# core.net
KiCad netlist of a schematic drawn in Altium Designer
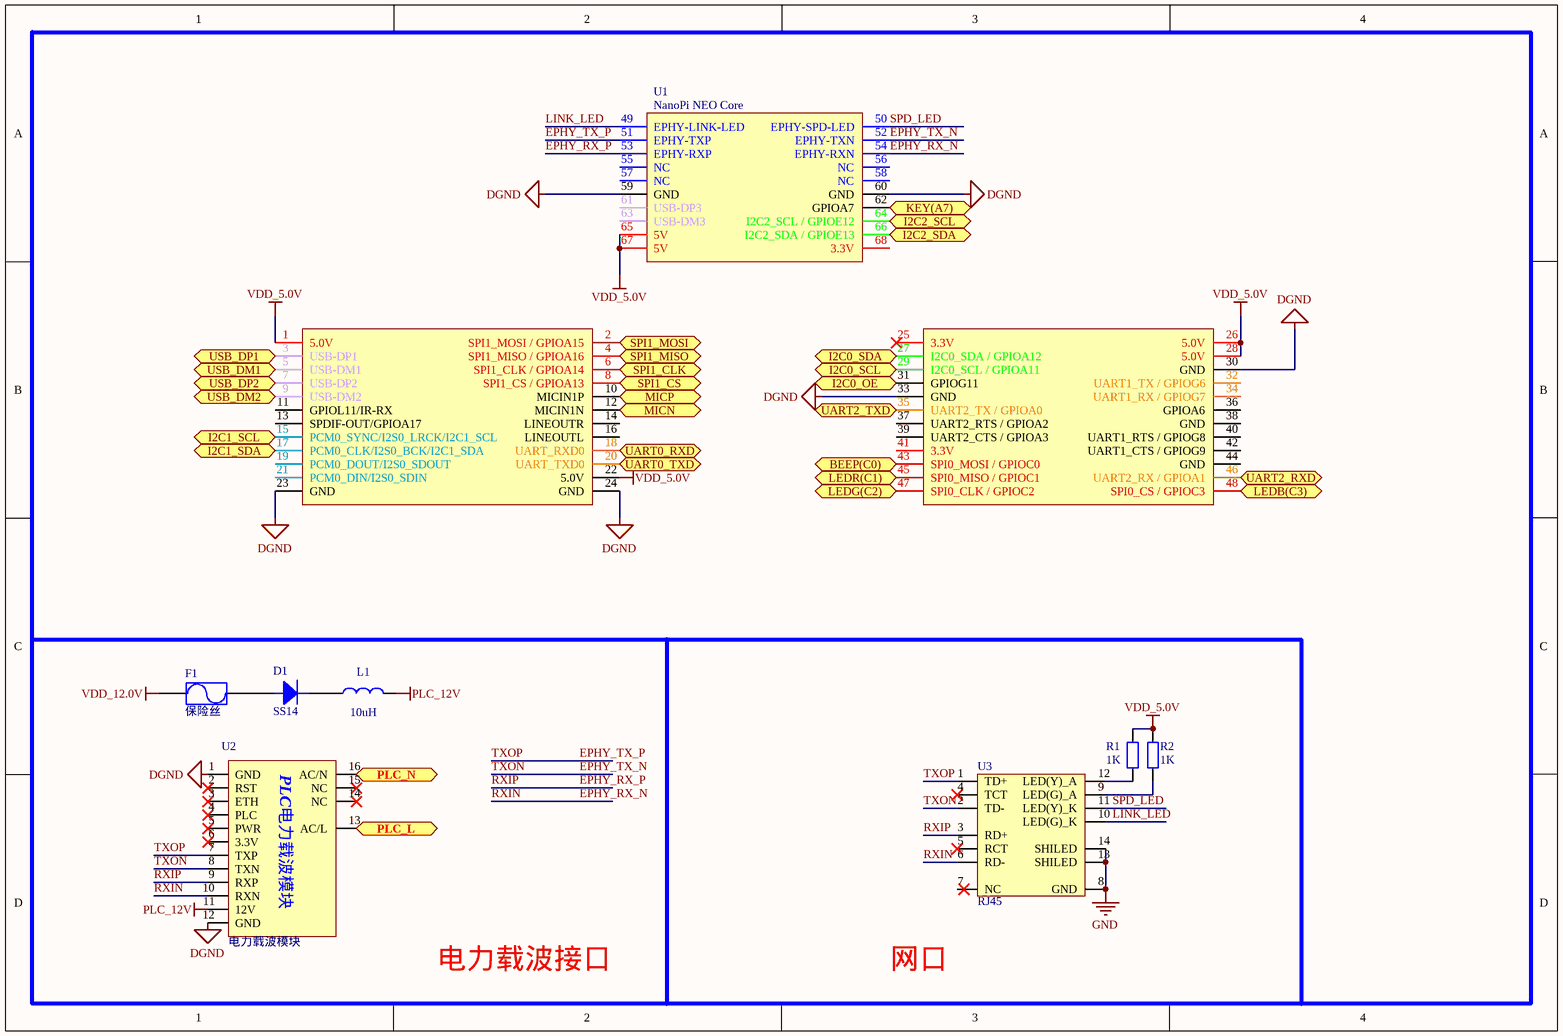
[diagram p0: core.SchDoc]

(export (version "E")
  (design (tool "Eeschema 10.0.6"))
  (components
    (comp (ref "D1")
      (value "SS14")
      (footprint "SMA/DO-214AC")
      (description "二极管")
      (libsource (lib "集大电协1.5") (part "Diode"))
    )
    (comp (ref "F1") (value "保险丝") (footprint "FUSE-1206") (libsource (lib "集大电协1.5") (part "Fuse")))
    (comp (ref "L1")
      (value "10uH")
      (footprint "1206L")
      (description "电感")
      (libsource (lib "集大电协1.5") (part "L"))
    )
    (comp (ref "R1")
      (value "1K")
      (footprint "0805R")
      (description "电阻")
      (libsource (lib "集大电协1.5") (part "Res"))
    )
    (comp (ref "R2")
      (value "1K")
      (footprint "0805R")
      (description "电阻")
      (libsource (lib "集大电协1.5") (part "Res"))
    )
    (comp (ref "U1")
      (value "NanoPi NEO Core")
      (footprint "NanoPi NEO Core")
      (libsource (lib "集大电协1.5") (part "NanoPi NEO Core"))
    )
    (comp (ref "U2")
      (value "电力载波模块")
      (footprint "电力载波模块6410")
      (libsource (lib "集大电协1.2") (part "电力载波模块6410"))
    )
    (comp (ref "U3") (value "RJ45") (footprint "RJ45") (libsource (lib "集大电协1.5") (part "RJ45")))
  )
  (nets
    (net (code "1") (name "/BEEP(C0)") (class "Default")
      (node (ref "U1") (pin "43") (pinfunction "SPI0_MOSI_/_GPIOC0_43") (pintype "passive"))
    )
    (net (code "2") (name "/EPHY_RX_N") (class "Default")
      (node (ref "U1") (pin "54") (pinfunction "EPHY-RXN_54") (pintype "passive"))
      (node (ref "U2") (pin "10") (pinfunction "RXN_10") (pintype "passive"))
      (node (ref "U3") (pin "6") (pinfunction "RD-_6") (pintype "passive"))
    )
    (net (code "3") (name "/EPHY_RX_P") (class "Default")
      (node (ref "U1") (pin "53") (pinfunction "EPHY-RXP_53") (pintype "passive"))
      (node (ref "U2") (pin "9") (pinfunction "RXP_9") (pintype "passive"))
      (node (ref "U3") (pin "3") (pinfunction "RD+_3") (pintype "passive"))
    )
    (net (code "4") (name "/EPHY_TX_N") (class "Default")
      (node (ref "U1") (pin "52") (pinfunction "EPHY-TXN_52") (pintype "passive"))
      (node (ref "U2") (pin "8") (pinfunction "TXN_8") (pintype "passive"))
      (node (ref "U3") (pin "2") (pinfunction "TD-_2") (pintype "passive"))
    )
    (net (code "5") (name "/EPHY_TX_P") (class "Default")
      (node (ref "U1") (pin "51") (pinfunction "EPHY-TXP_51") (pintype "passive"))
      (node (ref "U2") (pin "7") (pinfunction "TXP_7") (pintype "passive"))
      (node (ref "U3") (pin "1") (pinfunction "TD+_1") (pintype "passive"))
    )
    (net (code "6") (name "/I2C0_OE") (class "Default")
      (node (ref "U1") (pin "31") (pinfunction "GPIOG11_31") (pintype "passive"))
    )
    (net (code "7") (name "/I2C0_SCL") (class "Default")
      (node (ref "U1") (pin "29") (pinfunction "I2C0_SCL_/_GPIOA11_29") (pintype "passive"))
    )
    (net (code "8") (name "/I2C0_SDA") (class "Default")
      (node (ref "U1") (pin "27") (pinfunction "I2C0_SDA_/_GPIOA12_27") (pintype "passive"))
    )
    (net (code "9") (name "/I2C1_SCL") (class "Default")
      (node (ref "U1") (pin "15") (pinfunction "PCM0_SYNC/I2S0_LRCK/I2C1_SCL_15") (pintype "passive"))
    )
    (net (code "10") (name "/I2C1_SDA") (class "Default")
      (node (ref "U1") (pin "17") (pinfunction "PCM0_CLK/I2S0_BCK/I2C1_SDA_17") (pintype "passive"))
    )
    (net (code "11") (name "/I2C2_SCL") (class "Default")
      (node (ref "U1") (pin "64") (pinfunction "I2C2_SCL_/_GPIOE12_64") (pintype "passive"))
    )
    (net (code "12") (name "/I2C2_SDA") (class "Default")
      (node (ref "U1") (pin "66") (pinfunction "I2C2_SDA_/_GPIOE13_66") (pintype "passive"))
    )
    (net (code "13") (name "/KEY(A7)") (class "Default")
      (node (ref "U1") (pin "62") (pinfunction "GPIOA7_62") (pintype "passive"))
    )
    (net (code "14") (name "/LEDB(C3)") (class "Default")
      (node (ref "U1") (pin "48") (pinfunction "SPI0_CS_/_GPIOC3_48") (pintype "passive"))
    )
    (net (code "15") (name "/LEDG(C2)") (class "Default")
      (node (ref "U1") (pin "47") (pinfunction "SPI0_CLK_/_GPIOC2_47") (pintype "passive"))
    )
    (net (code "16") (name "/LEDR(C1)") (class "Default")
      (node (ref "U1") (pin "45") (pinfunction "SPI0_MISO_/_GPIOC1_45") (pintype "passive"))
    )
    (net (code "17") (name "/LINK_LED") (class "Default")
      (node (ref "U1") (pin "49") (pinfunction "EPHY-LINK-LED_49") (pintype "passive"))
      (node (ref "U3") (pin "10") (pinfunction "LED(G)_K_10") (pintype "passive"))
    )
    (net (code "18") (name "/MICN") (class "Default")
      (node (ref "U1") (pin "12") (pinfunction "MICIN1N_12") (pintype "passive"))
    )
    (net (code "19") (name "/MICP") (class "Default")
      (node (ref "U1") (pin "10") (pinfunction "MICIN1P_10") (pintype "passive"))
    )
    (net (code "20") (name "/PLC_L") (class "Default")
      (node (ref "U2") (pin "13") (pinfunction "AC/L_13") (pintype "passive"))
    )
    (net (code "21") (name "/PLC_N") (class "Default")
      (node (ref "U2") (pin "16") (pinfunction "AC/N_16") (pintype "passive"))
    )
    (net (code "22") (name "/SPD_LED") (class "Default")
      (node (ref "U1") (pin "50") (pinfunction "EPHY-SPD-LED_50") (pintype "passive"))
      (node (ref "U3") (pin "11") (pinfunction "LED(Y)_K_11") (pintype "passive"))
    )
    (net (code "23") (name "/SPI1_CLK") (class "Default")
      (node (ref "U1") (pin "6") (pinfunction "SPI1_CLK_/_GPIOA14_6") (pintype "passive"))
    )
    (net (code "24") (name "/SPI1_CS") (class "Default")
      (node (ref "U1") (pin "8") (pinfunction "SPI1_CS_/_GPIOA13_8") (pintype "passive"))
    )
    (net (code "25") (name "/SPI1_MISO") (class "Default")
      (node (ref "U1") (pin "4") (pinfunction "SPI1_MISO_/_GPIOA16_4") (pintype "passive"))
    )
    (net (code "26") (name "/SPI1_MOSI") (class "Default")
      (node (ref "U1") (pin "2") (pinfunction "SPI1_MOSI_/_GPIOA15_2") (pintype "passive"))
    )
    (net (code "27") (name "/UART0_RXD") (class "Default")
      (node (ref "U1") (pin "18") (pinfunction "UART_RXD0_18") (pintype "passive"))
    )
    (net (code "28") (name "/UART0_TXD") (class "Default")
      (node (ref "U1") (pin "20") (pinfunction "UART_TXD0_20") (pintype "passive"))
    )
    (net (code "29") (name "/UART2_RXD") (class "Default")
      (node (ref "U1") (pin "46") (pinfunction "UART2_RX_/_GPIOA1_46") (pintype "passive"))
    )
    (net (code "30") (name "/UART2_TXD") (class "Default")
      (node (ref "U1") (pin "35") (pinfunction "UART2_TX_/_GPIOA0_35") (pintype "passive"))
    )
    (net (code "31") (name "/USB_DM1") (class "Default")
      (node (ref "U1") (pin "5") (pinfunction "USB-DM1_5") (pintype "passive"))
    )
    (net (code "32") (name "/USB_DM2") (class "Default")
      (node (ref "U1") (pin "9") (pinfunction "USB-DM2_9") (pintype "passive"))
    )
    (net (code "33") (name "/USB_DP1") (class "Default")
      (node (ref "U1") (pin "3") (pinfunction "USB-DP1_3") (pintype "passive"))
    )
    (net (code "34") (name "/USB_DP2") (class "Default")
      (node (ref "U1") (pin "7") (pinfunction "USB-DP2_7") (pintype "passive"))
    )
    (net (code "35") (name "DGND") (class "Default")
      (node (ref "U1") (pin "23") (pinfunction "GND_23") (pintype "passive"))
      (node (ref "U1") (pin "24") (pinfunction "GND_24") (pintype "passive"))
      (node (ref "U1") (pin "30") (pinfunction "GND_30") (pintype "passive"))
      (node (ref "U1") (pin "33") (pinfunction "GND_33") (pintype "passive"))
      (node (ref "U1") (pin "59") (pinfunction "GND_59") (pintype "passive"))
      (node (ref "U1") (pin "60") (pinfunction "GND_60") (pintype "passive"))
      (node (ref "U2") (pin "1") (pinfunction "GND_1") (pintype "passive"))
      (node (ref "U2") (pin "12") (pinfunction "GND_12") (pintype "passive"))
    )
    (net (code "36") (name "GND") (class "Default")
      (node (ref "U3") (pin "13") (pinfunction "SHILED_13") (pintype "passive"))
      (node (ref "U3") (pin "14") (pinfunction "SHILED_14") (pintype "passive"))
      (node (ref "U3") (pin "8") (pinfunction "GND_8") (pintype "passive"))
    )
    (net (code "37") (name "Net-(D1-Pad1)") (class "Default")
      (node (ref "D1") (pin "1") (pintype "passive"))
      (node (ref "F1") (pin "2") (pinfunction "2_2") (pintype "passive"))
    )
    (net (code "38") (name "Net-(D1-Pad2)") (class "Default")
      (node (ref "D1") (pin "2") (pinfunction "2_2") (pintype "passive"))
      (node (ref "L1") (pin "1") (pinfunction "1_1") (pintype "passive"))
    )
    (net (code "39") (name "Net-(U3-LED(G)_A)") (class "Default")
      (node (ref "R2") (pin "2") (pinfunction "2_2") (pintype "passive"))
      (node (ref "U3") (pin "9") (pinfunction "LED(G)_A_9") (pintype "passive"))
    )
    (net (code "40") (name "Net-(U3-LED(Y)_A)") (class "Default")
      (node (ref "R1") (pin "2") (pinfunction "2_2") (pintype "passive"))
      (node (ref "U3") (pin "12") (pinfunction "LED(Y)_A_12") (pintype "passive"))
    )
    (net (code "41") (name "PLC_12V") (class "Default")
      (node (ref "L1") (pin "2") (pinfunction "2_2") (pintype "passive"))
      (node (ref "U2") (pin "11") (pinfunction "12V_11") (pintype "passive"))
    )
    (net (code "42") (name "VDD_5.0V") (class "Default")
      (node (ref "R1") (pin "1") (pinfunction "1_1") (pintype "passive"))
      (node (ref "R2") (pin "1") (pinfunction "1_1") (pintype "passive"))
      (node (ref "U1") (pin "1") (pinfunction "5.0V_1") (pintype "passive"))
      (node (ref "U1") (pin "22") (pinfunction "5.0V_22") (pintype "passive"))
      (node (ref "U1") (pin "26") (pinfunction "5.0V_26") (pintype "passive"))
      (node (ref "U1") (pin "28") (pinfunction "5.0V_28") (pintype "passive"))
      (node (ref "U1") (pin "65") (pinfunction "5V_65") (pintype "passive"))
      (node (ref "U1") (pin "67") (pinfunction "5V_67") (pintype "passive"))
    )
    (net (code "43") (name "VDD_12.0V") (class "Default")
      (node (ref "F1") (pin "1") (pinfunction "1_1") (pintype "passive"))
    )
    (net (code "44") (name "unconnected-(U1-3.3V-Pad25)") (class "Default")
      (node (ref "U1") (pin "25") (pinfunction "3.3V_25") (pintype "passive+no_connect"))
    )
    (net (code "45") (name "unconnected-(U1-3.3V-Pad41)") (class "Default")
      (node (ref "U1") (pin "41") (pinfunction "3.3V_41") (pintype "passive"))
    )
    (net (code "46") (name "unconnected-(U1-3.3V-Pad68)") (class "Default")
      (node (ref "U1") (pin "68") (pinfunction "3.3V_68") (pintype "passive"))
    )
    (net (code "47") (name "unconnected-(U1-GND-Pad38)") (class "Default")
      (node (ref "U1") (pin "38") (pinfunction "GND_38") (pintype "passive"))
    )
    (net (code "48") (name "unconnected-(U1-GND-Pad44)") (class "Default")
      (node (ref "U1") (pin "44") (pinfunction "GND_44") (pintype "passive"))
    )
    (net (code "49") (name "unconnected-(U1-GPIOA6-Pad36)") (class "Default")
      (node (ref "U1") (pin "36") (pinfunction "GPIOA6_36") (pintype "passive"))
    )
    (net (code "50") (name "unconnected-(U1-GPIOL11{slash}IR-RX-Pad11)") (class "Default")
      (node (ref "U1") (pin "11") (pinfunction "GPIOL11/IR-RX_11") (pintype "passive"))
    )
    (net (code "51") (name "unconnected-(U1-LINEOUTL-Pad16)") (class "Default")
      (node (ref "U1") (pin "16") (pinfunction "LINEOUTL_16") (pintype "passive"))
    )
    (net (code "52") (name "unconnected-(U1-LINEOUTR-Pad14)") (class "Default")
      (node (ref "U1") (pin "14") (pinfunction "LINEOUTR_14") (pintype "passive"))
    )
    (net (code "53") (name "unconnected-(U1-NC-Pad55)") (class "Default")
      (node (ref "U1") (pin "55") (pinfunction "NC_55") (pintype "passive"))
    )
    (net (code "54") (name "unconnected-(U1-NC-Pad56)") (class "Default")
      (node (ref "U1") (pin "56") (pinfunction "NC_56") (pintype "passive"))
    )
    (net (code "55") (name "unconnected-(U1-NC-Pad57)") (class "Default")
      (node (ref "U1") (pin "57") (pinfunction "NC_57") (pintype "passive"))
    )
    (net (code "56") (name "unconnected-(U1-NC-Pad58)") (class "Default")
      (node (ref "U1") (pin "58") (pinfunction "NC_58") (pintype "passive"))
    )
    (net (code "57") (name "unconnected-(U1-PCM0_DIN{slash}I2S0_SDIN-Pad21)") (class "Default")
      (node (ref "U1") (pin "21") (pinfunction "PCM0_DIN/I2S0_SDIN_21") (pintype "passive"))
    )
    (net (code "58") (name "unconnected-(U1-PCM0_DOUT{slash}I2S0_SDOUT-Pad19)") (class "Default")
      (node (ref "U1") (pin "19") (pinfunction "PCM0_DOUT/I2S0_SDOUT_19") (pintype "passive"))
    )
    (net (code "59") (name "unconnected-(U1-SPDIF-OUT{slash}GPIOA17-Pad13)") (class "Default")
      (node (ref "U1") (pin "13") (pinfunction "SPDIF-OUT/GPIOA17_13") (pintype "passive"))
    )
    (net (code "60") (name "unconnected-(U1-UART1_CTS_{slash}_GPIOG9-Pad42)") (class "Default")
      (node (ref "U1") (pin "42") (pinfunction "UART1_CTS_/_GPIOG9_42") (pintype "passive"))
    )
    (net (code "61") (name "unconnected-(U1-UART1_RTS_{slash}_GPIOG8-Pad40)") (class "Default")
      (node (ref "U1") (pin "40") (pinfunction "UART1_RTS_/_GPIOG8_40") (pintype "passive"))
    )
    (net (code "62") (name "unconnected-(U1-UART1_RX_{slash}_GPIOG7-Pad34)") (class "Default")
      (node (ref "U1") (pin "34") (pinfunction "UART1_RX_/_GPIOG7_34") (pintype "passive"))
    )
    (net (code "63") (name "unconnected-(U1-UART1_TX_{slash}_GPIOG6-Pad32)") (class "Default")
      (node (ref "U1") (pin "32") (pinfunction "UART1_TX_/_GPIOG6_32") (pintype "passive"))
    )
    (net (code "64") (name "unconnected-(U1-UART2_CTS_{slash}_GPIOA3-Pad39)") (class "Default")
      (node (ref "U1") (pin "39") (pinfunction "UART2_CTS_/_GPIOA3_39") (pintype "passive"))
    )
    (net (code "65") (name "unconnected-(U1-UART2_RTS_{slash}_GPIOA2-Pad37)") (class "Default")
      (node (ref "U1") (pin "37") (pinfunction "UART2_RTS_/_GPIOA2_37") (pintype "passive"))
    )
    (net (code "66") (name "unconnected-(U1-USB-DM3-Pad63)") (class "Default")
      (node (ref "U1") (pin "63") (pinfunction "USB-DM3_63") (pintype "passive"))
    )
    (net (code "67") (name "unconnected-(U1-USB-DP3-Pad61)") (class "Default")
      (node (ref "U1") (pin "61") (pinfunction "USB-DP3_61") (pintype "passive"))
    )
    (net (code "68") (name "unconnected-(U2-3.3V-Pad6)") (class "Default")
      (node (ref "U2") (pin "6") (pinfunction "3.3V_6") (pintype "passive+no_connect"))
    )
    (net (code "69") (name "unconnected-(U2-ETH-Pad3)") (class "Default")
      (node (ref "U2") (pin "3") (pinfunction "ETH_3") (pintype "passive+no_connect"))
    )
    (net (code "70") (name "unconnected-(U2-NC-Pad14)") (class "Default")
      (node (ref "U2") (pin "14") (pinfunction "NC_14") (pintype "passive+no_connect"))
    )
    (net (code "71") (name "unconnected-(U2-NC-Pad15)") (class "Default")
      (node (ref "U2") (pin "15") (pinfunction "NC_15") (pintype "passive+no_connect"))
    )
    (net (code "72") (name "unconnected-(U2-PLC-Pad4)") (class "Default")
      (node (ref "U2") (pin "4") (pinfunction "PLC_4") (pintype "passive+no_connect"))
    )
    (net (code "73") (name "unconnected-(U2-PWR-Pad5)") (class "Default")
      (node (ref "U2") (pin "5") (pinfunction "PWR_5") (pintype "passive+no_connect"))
    )
    (net (code "74") (name "unconnected-(U2-RST-Pad2)") (class "Default")
      (node (ref "U2") (pin "2") (pinfunction "RST_2") (pintype "passive+no_connect"))
    )
    (net (code "75") (name "unconnected-(U3-NC-Pad7)") (class "Default")
      (node (ref "U3") (pin "7") (pinfunction "NC_7") (pintype "passive"))
    )
    (net (code "76") (name "unconnected-(U3-RCT-Pad5)") (class "Default")
      (node (ref "U3") (pin "5") (pinfunction "RCT_5") (pintype "passive+no_connect"))
    )
    (net (code "77") (name "unconnected-(U3-TCT-Pad4)") (class "Default")
      (node (ref "U3") (pin "4") (pinfunction "TCT_4") (pintype "passive+no_connect"))
    )
  )
)
